# mapleSDuino-V0_2_022-eagle7.net
KiCad netlist of a schematic drawn in EAGLE
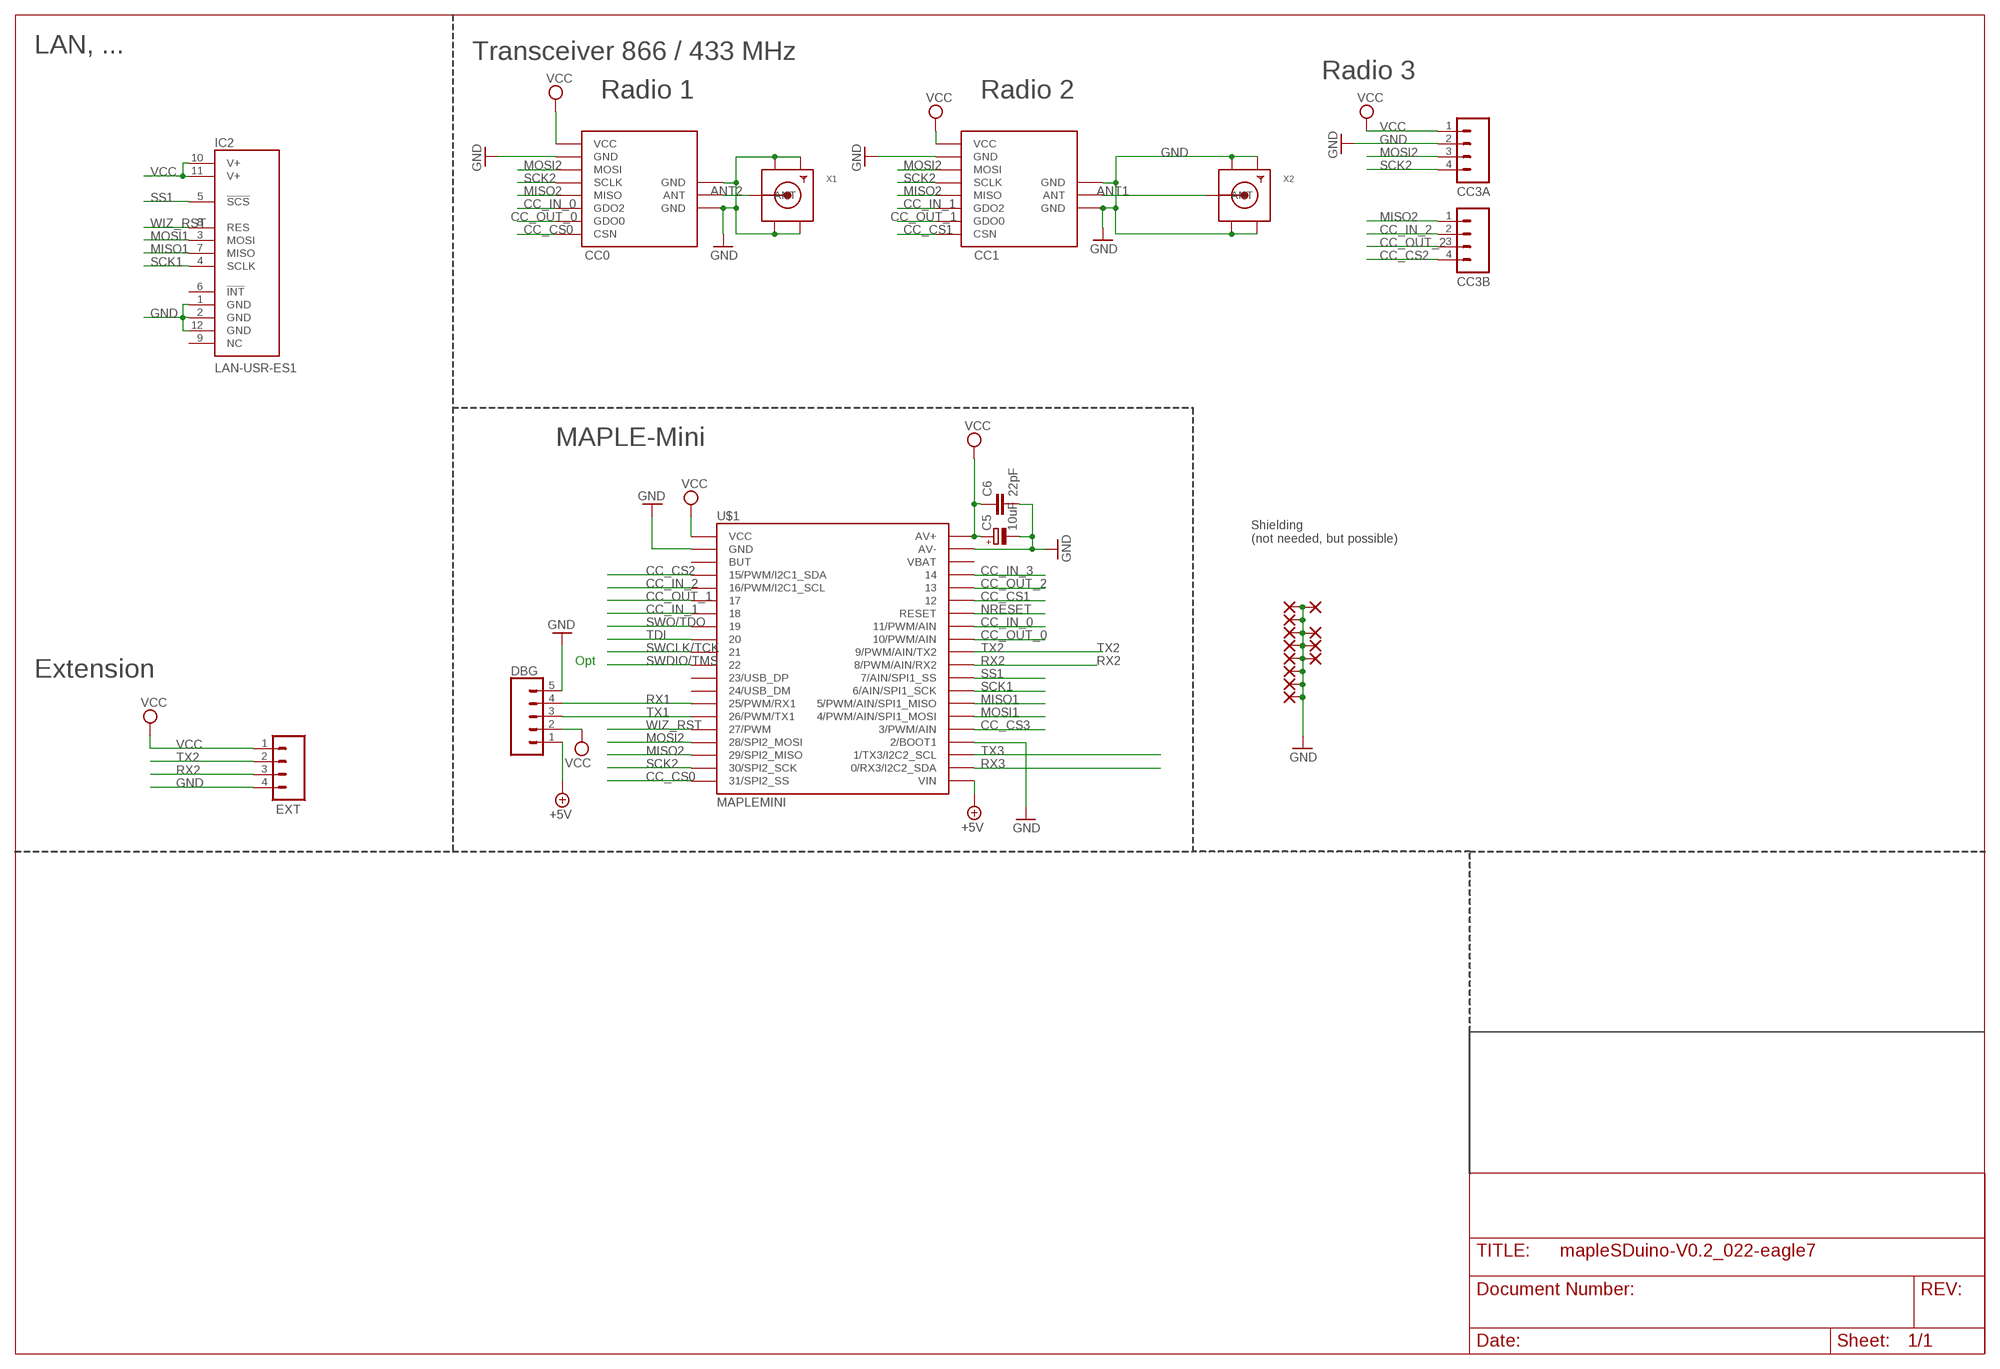
[diagram p0: schematic, sheet 1]

(export (version "E")
  (design (tool "Eeschema 10.0.6"))
  (components
    (comp (ref "C5")
      (value "10uF")
      (footprint "eagle-import:R_2012-12W")
      (libsource (lib "eagle-import") (part "CPOL-EUR/2012-12W"))
    )
    (comp (ref "C6")
      (value "22pF")
      (footprint "eagle-import:C0805")
      (libsource (lib "eagle-import") (part "C-EUC0805"))
    )
    (comp (ref "CC0")
      (value "CC1101")
      (footprint "eagle-import:CC1101_MODULE1_SMD")
      (libsource (lib "eagle-import") (part "CC1101_MODULE1SMD"))
    )
    (comp (ref "CC1")
      (value "CC1101_MODULE1SMD")
      (footprint "eagle-import:CC1101_MODULE1_SMD")
      (libsource (lib "eagle-import") (part "CC1101_MODULE1SMD"))
    )
    (comp (ref "CC3A")
      (value "CONN_04PTH")
      (footprint "eagle-import:1X04")
      (libsource (lib "eagle-import") (part "CONN_04PTH"))
    )
    (comp (ref "CC3B")
      (value "CONN_04PTH")
      (footprint "eagle-import:1X04")
      (libsource (lib "eagle-import") (part "CONN_04PTH"))
    )
    (comp (ref "DBG")
      (value "CONN_05LOCK")
      (footprint "eagle-import:1X05_LOCK")
      (libsource (lib "eagle-import") (part "CONN_05LOCK"))
    )
    (comp (ref "EXT")
      (value "CONN_04PTH")
      (footprint "eagle-import:1X04")
      (libsource (lib "eagle-import") (part "CONN_04PTH"))
    )
    (comp (ref "IC2")
      (value "LAN-USR-ES1")
      (footprint "eagle-import:USR-ES1")
      (libsource (lib "eagle-import") (part "LAN-USR-ES1"))
    )
    (comp (ref "PAD1")
      (value "WIREPADSMD1,27-254")
      (footprint "eagle-import:SMD1,27-2,54")
      (libsource (lib "eagle-import") (part "WIREPADSMD1,27-254"))
    )
    (comp (ref "PAD2")
      (value "WIREPADSMD1,27-254")
      (footprint "eagle-import:SMD1,27-2,54")
      (libsource (lib "eagle-import") (part "WIREPADSMD1,27-254"))
    )
    (comp (ref "PAD3")
      (value "WIREPADSMD1,27-254")
      (footprint "eagle-import:SMD1,27-2,54")
      (libsource (lib "eagle-import") (part "WIREPADSMD1,27-254"))
    )
    (comp (ref "PAD4")
      (value "WIREPADSMD1,27-254")
      (footprint "eagle-import:SMD1,27-2,54")
      (libsource (lib "eagle-import") (part "WIREPADSMD1,27-254"))
    )
    (comp (ref "PAD5")
      (value "WIREPADSMD1,27-254")
      (footprint "eagle-import:SMD1,27-2,54")
      (libsource (lib "eagle-import") (part "WIREPADSMD1,27-254"))
    )
    (comp (ref "PAD6")
      (value "WIREPADSMD1,27-254")
      (footprint "eagle-import:SMD1,27-2,54")
      (libsource (lib "eagle-import") (part "WIREPADSMD1,27-254"))
    )
    (comp (ref "PAD7")
      (value "WIREPADSMD1,27-254")
      (footprint "eagle-import:SMD1,27-2,54")
      (libsource (lib "eagle-import") (part "WIREPADSMD1,27-254"))
    )
    (comp (ref "PAD8")
      (value "WIREPADSMD1,27-254")
      (footprint "eagle-import:SMD1,27-2,54")
      (libsource (lib "eagle-import") (part "WIREPADSMD1,27-254"))
    )
    (comp (ref "PAD9")
      (value "WIREPADSMD1,27-254")
      (footprint "eagle-import:SMD1,27-2,54")
      (libsource (lib "eagle-import") (part "WIREPADSMD1,27-254"))
    )
    (comp (ref "PAD10")
      (value "WIREPADSMD1,27-254")
      (footprint "eagle-import:SMD1,27-2,54")
      (libsource (lib "eagle-import") (part "WIREPADSMD1,27-254"))
    )
    (comp (ref "PAD11")
      (value "WIREPADSMD1,27-254")
      (footprint "eagle-import:SMD1,27-2,54")
      (libsource (lib "eagle-import") (part "WIREPADSMD1,27-254"))
    )
    (comp (ref "PAD12")
      (value "WIREPADSMD1,27-254")
      (footprint "eagle-import:SMD1,27-2,54")
      (libsource (lib "eagle-import") (part "WIREPADSMD1,27-254"))
    )
    (comp (ref "U$1")
      (value "MAPLEMINI")
      (footprint "eagle-import:20-DIP")
      (libsource (lib "eagle-import") (part "MAPLEMINI"))
    )
    (comp (ref "X1")
      (value "SMACONNECTOR_EDGE")
      (footprint "eagle-import:SMA_EDGELAUNCH")
      (libsource (lib "eagle-import") (part "SMACONNECTOR_EDGE"))
    )
    (comp (ref "X2")
      (value "SMACONNECTOR_EDGE")
      (footprint "eagle-import:SMA_EDGELAUNCH")
      (libsource (lib "eagle-import") (part "SMACONNECTOR_EDGE"))
    )
  )
  (nets
    (net (code "1") (name "+5V") (class "Default")
      (node (ref "DBG") (pin "1") (pinfunction "1_1") (pintype "passive"))
      (node (ref "U$1") (pin "21") (pinfunction "VIN_21") (pintype "bidirectional"))
    )
    (net (code "2") (name "/ANT1") (class "Default")
      (node (ref "CC1") (pin "ANT") (pinfunction "ANT_ANT") (pintype "output"))
      (node (ref "X2") (pin "P") (pinfunction "ANT_P") (pintype "bidirectional"))
    )
    (net (code "3") (name "/ANT2") (class "Default")
      (node (ref "CC0") (pin "ANT") (pinfunction "ANT_ANT") (pintype "output"))
      (node (ref "X1") (pin "P") (pinfunction "ANT_P") (pintype "bidirectional"))
    )
    (net (code "4") (name "/CC_CS0") (class "Default")
      (node (ref "CC0") (pin "CSN") (pinfunction "CSN_CSN") (pintype "bidirectional"))
      (node (ref "U$1") (pin "20") (pinfunction "31/SPI2_SS_20") (pintype "bidirectional"))
    )
    (net (code "5") (name "/CC_CS1") (class "Default")
      (node (ref "CC1") (pin "CSN") (pinfunction "CSN_CSN") (pintype "bidirectional"))
      (node (ref "U$1") (pin "35") (pinfunction "12_35") (pintype "bidirectional"))
    )
    (net (code "6") (name "/CC_CS2") (class "Default")
      (node (ref "CC3B") (pin "4") (pinfunction "4_4") (pintype "passive"))
      (node (ref "U$1") (pin "4") (pinfunction "15/PWM/I2C1_SDA_4") (pintype "bidirectional"))
    )
    (net (code "7") (name "/CC_CS3") (class "Default")
      (node (ref "U$1") (pin "25") (pinfunction "3/PWM/AIN_25") (pintype "bidirectional"))
    )
    (net (code "8") (name "/CC_IN_0") (class "Default")
      (node (ref "CC0") (pin "GDO2") (pinfunction "GDO2_GDO2") (pintype "bidirectional"))
      (node (ref "U$1") (pin "33") (pinfunction "11/PWM/AIN_33") (pintype "bidirectional"))
    )
    (net (code "9") (name "/CC_IN_1") (class "Default")
      (node (ref "CC1") (pin "GDO2") (pinfunction "GDO2_GDO2") (pintype "bidirectional"))
      (node (ref "U$1") (pin "7") (pinfunction "18_7") (pintype "bidirectional"))
    )
    (net (code "10") (name "/CC_IN_2") (class "Default")
      (node (ref "CC3B") (pin "2") (pinfunction "2_2") (pintype "passive"))
      (node (ref "U$1") (pin "5") (pinfunction "16/PWM/I2C1_SCL_5") (pintype "bidirectional"))
    )
    (net (code "11") (name "/CC_IN_3") (class "Default")
      (node (ref "U$1") (pin "37") (pinfunction "14_37") (pintype "bidirectional"))
    )
    (net (code "12") (name "/CC_OUT_0") (class "Default")
      (node (ref "CC0") (pin "GDO0") (pinfunction "GDO0_GDO0") (pintype "bidirectional"))
      (node (ref "U$1") (pin "32") (pinfunction "10/PWM/AIN_32") (pintype "bidirectional"))
    )
    (net (code "13") (name "/CC_OUT_1") (class "Default")
      (node (ref "CC1") (pin "GDO0") (pinfunction "GDO0_GDO0") (pintype "bidirectional"))
      (node (ref "U$1") (pin "6") (pinfunction "17_6") (pintype "bidirectional"))
    )
    (net (code "14") (name "/CC_OUT_2") (class "Default")
      (node (ref "CC3B") (pin "3") (pinfunction "3_3") (pintype "passive"))
      (node (ref "U$1") (pin "36") (pinfunction "13_36") (pintype "bidirectional"))
    )
    (net (code "15") (name "/MISO1") (class "Default")
      (node (ref "IC2") (pin "7") (pinfunction "MISO_7") (pintype "bidirectional"))
      (node (ref "U$1") (pin "27") (pinfunction "5/PWM/AIN/SPI1_MISO_27") (pintype "bidirectional"))
    )
    (net (code "16") (name "/MISO2") (class "Default")
      (node (ref "CC0") (pin "MISO") (pinfunction "MISO_MISO") (pintype "bidirectional"))
      (node (ref "CC1") (pin "MISO") (pinfunction "MISO_MISO") (pintype "bidirectional"))
      (node (ref "CC3B") (pin "1") (pinfunction "1_1") (pintype "passive"))
      (node (ref "U$1") (pin "18") (pinfunction "29/SPI2_MISO_18") (pintype "bidirectional"))
    )
    (net (code "17") (name "/MOSI1") (class "Default")
      (node (ref "IC2") (pin "3") (pinfunction "MOSI_3") (pintype "bidirectional"))
      (node (ref "U$1") (pin "26") (pinfunction "4/PWM/AIN/SPI1_MOSI_26") (pintype "bidirectional"))
    )
    (net (code "18") (name "/MOSI2") (class "Default")
      (node (ref "CC0") (pin "MOSI") (pinfunction "MOSI_MOSI") (pintype "bidirectional"))
      (node (ref "CC1") (pin "MOSI") (pinfunction "MOSI_MOSI") (pintype "bidirectional"))
      (node (ref "CC3A") (pin "3") (pinfunction "3_3") (pintype "passive"))
      (node (ref "U$1") (pin "17") (pinfunction "28/SPI2_MOSI_17") (pintype "bidirectional"))
    )
    (net (code "19") (name "/NRESET") (class "Default")
      (node (ref "U$1") (pin "34") (pinfunction "RESET_34") (pintype "bidirectional"))
    )
    (net (code "20") (name "/RX1") (class "Default")
      (node (ref "DBG") (pin "4") (pinfunction "4_4") (pintype "passive"))
      (node (ref "U$1") (pin "14") (pinfunction "25/PWM/RX1_14") (pintype "bidirectional"))
    )
    (net (code "21") (name "/RX2") (class "Default")
      (node (ref "EXT") (pin "3") (pinfunction "3_3") (pintype "passive"))
      (node (ref "U$1") (pin "30") (pinfunction "8/PWM/AIN/RX2_30") (pintype "bidirectional"))
    )
    (net (code "22") (name "/RX3") (class "Default")
      (node (ref "U$1") (pin "22") (pinfunction "0/RX3/I2C2_SDA_22") (pintype "bidirectional"))
    )
    (net (code "23") (name "/SCK1") (class "Default")
      (node (ref "IC2") (pin "4") (pinfunction "SCLK_4") (pintype "input"))
      (node (ref "U$1") (pin "28") (pinfunction "6/AIN/SPI1_SCK_28") (pintype "bidirectional"))
    )
    (net (code "24") (name "/SCK2") (class "Default")
      (node (ref "CC0") (pin "SCLK") (pinfunction "SCLK_SCLK") (pintype "bidirectional"))
      (node (ref "CC1") (pin "SCLK") (pinfunction "SCLK_SCLK") (pintype "bidirectional"))
      (node (ref "CC3A") (pin "4") (pinfunction "4_4") (pintype "passive"))
      (node (ref "U$1") (pin "19") (pinfunction "30/SPI2_SCK_19") (pintype "bidirectional"))
    )
    (net (code "25") (name "/SS1") (class "Default")
      (node (ref "IC2") (pin "5") (pinfunction "~{SCS}_5") (pintype "input"))
      (node (ref "U$1") (pin "29") (pinfunction "7/AIN/SPI1_SS_29") (pintype "bidirectional"))
    )
    (net (code "26") (name "/SWCLK{slash}TCK") (class "Default")
      (node (ref "U$1") (pin "10") (pinfunction "21_10") (pintype "bidirectional"))
    )
    (net (code "27") (name "/SWDIO{slash}TMS") (class "Default")
      (node (ref "U$1") (pin "11") (pinfunction "22_11") (pintype "bidirectional"))
    )
    (net (code "28") (name "/SWO{slash}TDO") (class "Default")
      (node (ref "U$1") (pin "8") (pinfunction "19_8") (pintype "bidirectional"))
    )
    (net (code "29") (name "/TDI") (class "Default")
      (node (ref "U$1") (pin "9") (pinfunction "20_9") (pintype "bidirectional"))
    )
    (net (code "30") (name "/TX1") (class "Default")
      (node (ref "DBG") (pin "3") (pinfunction "3_3") (pintype "passive"))
      (node (ref "U$1") (pin "15") (pinfunction "26/PWM/TX1_15") (pintype "bidirectional"))
    )
    (net (code "31") (name "/TX2") (class "Default")
      (node (ref "EXT") (pin "2") (pinfunction "2_2") (pintype "passive"))
      (node (ref "U$1") (pin "31") (pinfunction "9/PWM/AIN/TX2_31") (pintype "bidirectional"))
    )
    (net (code "32") (name "/TX3") (class "Default")
      (node (ref "U$1") (pin "23") (pinfunction "1/TX3/I2C2_SCL_23") (pintype "bidirectional"))
    )
    (net (code "33") (name "/WIZ_RST") (class "Default")
      (node (ref "IC2") (pin "8") (pinfunction "RES_8") (pintype "input"))
      (node (ref "U$1") (pin "16") (pinfunction "27/PWM_16") (pintype "bidirectional"))
    )
    (net (code "34") (name "GND") (class "Default")
      (node (ref "C5") (pin "-") (pinfunction "-_-") (pintype "passive"))
      (node (ref "C6") (pin "2") (pinfunction "2_2") (pintype "passive"))
      (node (ref "CC0") (pin "GND@0") (pinfunction "GND_GND@0") (pintype "power_in"))
      (node (ref "CC0") (pin "GND@1") (pinfunction "GND_GND@1") (pintype "power_in"))
      (node (ref "CC0") (pin "GND@2") (pinfunction "GND_GND@2") (pintype "power_in"))
      (node (ref "CC1") (pin "GND@0") (pinfunction "GND_GND@0") (pintype "power_in"))
      (node (ref "CC1") (pin "GND@1") (pinfunction "GND_GND@1") (pintype "power_in"))
      (node (ref "CC1") (pin "GND@2") (pinfunction "GND_GND@2") (pintype "power_in"))
      (node (ref "CC3A") (pin "2") (pinfunction "2_2") (pintype "passive"))
      (node (ref "DBG") (pin "5") (pinfunction "5_5") (pintype "passive"))
      (node (ref "EXT") (pin "4") (pinfunction "4_4") (pintype "passive"))
      (node (ref "IC2") (pin "1") (pinfunction "GND_1") (pintype "power_in"))
      (node (ref "IC2") (pin "12") (pinfunction "GND_12") (pintype "power_in"))
      (node (ref "IC2") (pin "2") (pinfunction "GND_2") (pintype "power_in"))
      (node (ref "PAD1") (pin "1") (pinfunction "P_1") (pintype "passive"))
      (node (ref "PAD10") (pin "1") (pinfunction "P_1") (pintype "passive"))
      (node (ref "PAD11") (pin "1") (pinfunction "P_1") (pintype "passive"))
      (node (ref "PAD12") (pin "1") (pinfunction "P_1") (pintype "passive"))
      (node (ref "PAD2") (pin "1") (pinfunction "P_1") (pintype "passive"))
      (node (ref "PAD3") (pin "1") (pinfunction "P_1") (pintype "passive"))
      (node (ref "PAD4") (pin "1") (pinfunction "P_1") (pintype "passive"))
      (node (ref "PAD5") (pin "1") (pinfunction "P_1") (pintype "passive"))
      (node (ref "PAD6") (pin "1") (pinfunction "P_1") (pintype "passive"))
      (node (ref "PAD7") (pin "1") (pinfunction "P_1") (pintype "passive"))
      (node (ref "PAD8") (pin "1") (pinfunction "P_1") (pintype "passive"))
      (node (ref "PAD9") (pin "1") (pinfunction "P_1") (pintype "passive"))
      (node (ref "U$1") (pin "2") (pinfunction "GND_2") (pintype "bidirectional"))
      (node (ref "U$1") (pin "24") (pinfunction "2/BOOT1_24") (pintype "bidirectional"))
      (node (ref "U$1") (pin "39") (pinfunction "AV-_39") (pintype "bidirectional"))
      (node (ref "X1") (pin "GND@1") (pinfunction "GND4_GND@1") (pintype "power_in"))
      (node (ref "X1") (pin "GND@2") (pinfunction "GND3_GND@2") (pintype "power_in"))
      (node (ref "X1") (pin "GND@3") (pinfunction "GND2_GND@3") (pintype "power_in"))
      (node (ref "X1") (pin "GND@4") (pinfunction "GND1_GND@4") (pintype "power_in"))
      (node (ref "X2") (pin "GND@1") (pinfunction "GND4_GND@1") (pintype "power_in"))
      (node (ref "X2") (pin "GND@2") (pinfunction "GND3_GND@2") (pintype "power_in"))
      (node (ref "X2") (pin "GND@3") (pinfunction "GND2_GND@3") (pintype "power_in"))
      (node (ref "X2") (pin "GND@4") (pinfunction "GND1_GND@4") (pintype "power_in"))
    )
    (net (code "35") (name "VCC") (class "Default")
      (node (ref "C5") (pin "+") (pinfunction "+_+") (pintype "passive"))
      (node (ref "C6") (pin "1") (pinfunction "1_1") (pintype "passive"))
      (node (ref "CC0") (pin "VCC") (pinfunction "VCC_VCC") (pintype "power_in"))
      (node (ref "CC1") (pin "VCC") (pinfunction "VCC_VCC") (pintype "power_in"))
      (node (ref "CC3A") (pin "1") (pinfunction "1_1") (pintype "passive"))
      (node (ref "DBG") (pin "2") (pinfunction "2_2") (pintype "passive"))
      (node (ref "EXT") (pin "1") (pinfunction "1_1") (pintype "passive"))
      (node (ref "IC2") (pin "10") (pinfunction "V+_10") (pintype "power_in"))
      (node (ref "IC2") (pin "11") (pinfunction "V+_11") (pintype "power_in"))
      (node (ref "U$1") (pin "1") (pinfunction "VCC_1") (pintype "bidirectional"))
      (node (ref "U$1") (pin "40") (pinfunction "AV+_40") (pintype "bidirectional"))
    )
    (net (code "36") (name "unconnected-(IC2-NC-Pad9)") (class "Default")
      (node (ref "IC2") (pin "9") (pinfunction "NC_9") (pintype "no_connect"))
    )
    (net (code "37") (name "unconnected-(IC2-~{INT}-Pad6)") (class "Default")
      (node (ref "IC2") (pin "6") (pinfunction "~{INT}_6") (pintype "output"))
    )
    (net (code "38") (name "unconnected-(U$1-23{slash}USB_DP-Pad12)") (class "Default")
      (node (ref "U$1") (pin "12") (pinfunction "23/USB_DP_12") (pintype "bidirectional"))
    )
    (net (code "39") (name "unconnected-(U$1-24{slash}USB_DM-Pad13)") (class "Default")
      (node (ref "U$1") (pin "13") (pinfunction "24/USB_DM_13") (pintype "bidirectional"))
    )
    (net (code "40") (name "unconnected-(U$1-BUT-Pad3)") (class "Default")
      (node (ref "U$1") (pin "3") (pinfunction "BUT_3") (pintype "bidirectional"))
    )
    (net (code "41") (name "unconnected-(U$1-VBAT-Pad38)") (class "Default")
      (node (ref "U$1") (pin "38") (pinfunction "VBAT_38") (pintype "bidirectional"))
    )
  )
)
